# AnalogPSU.net
KiCad netlist of a schematic drawn in EAGLE
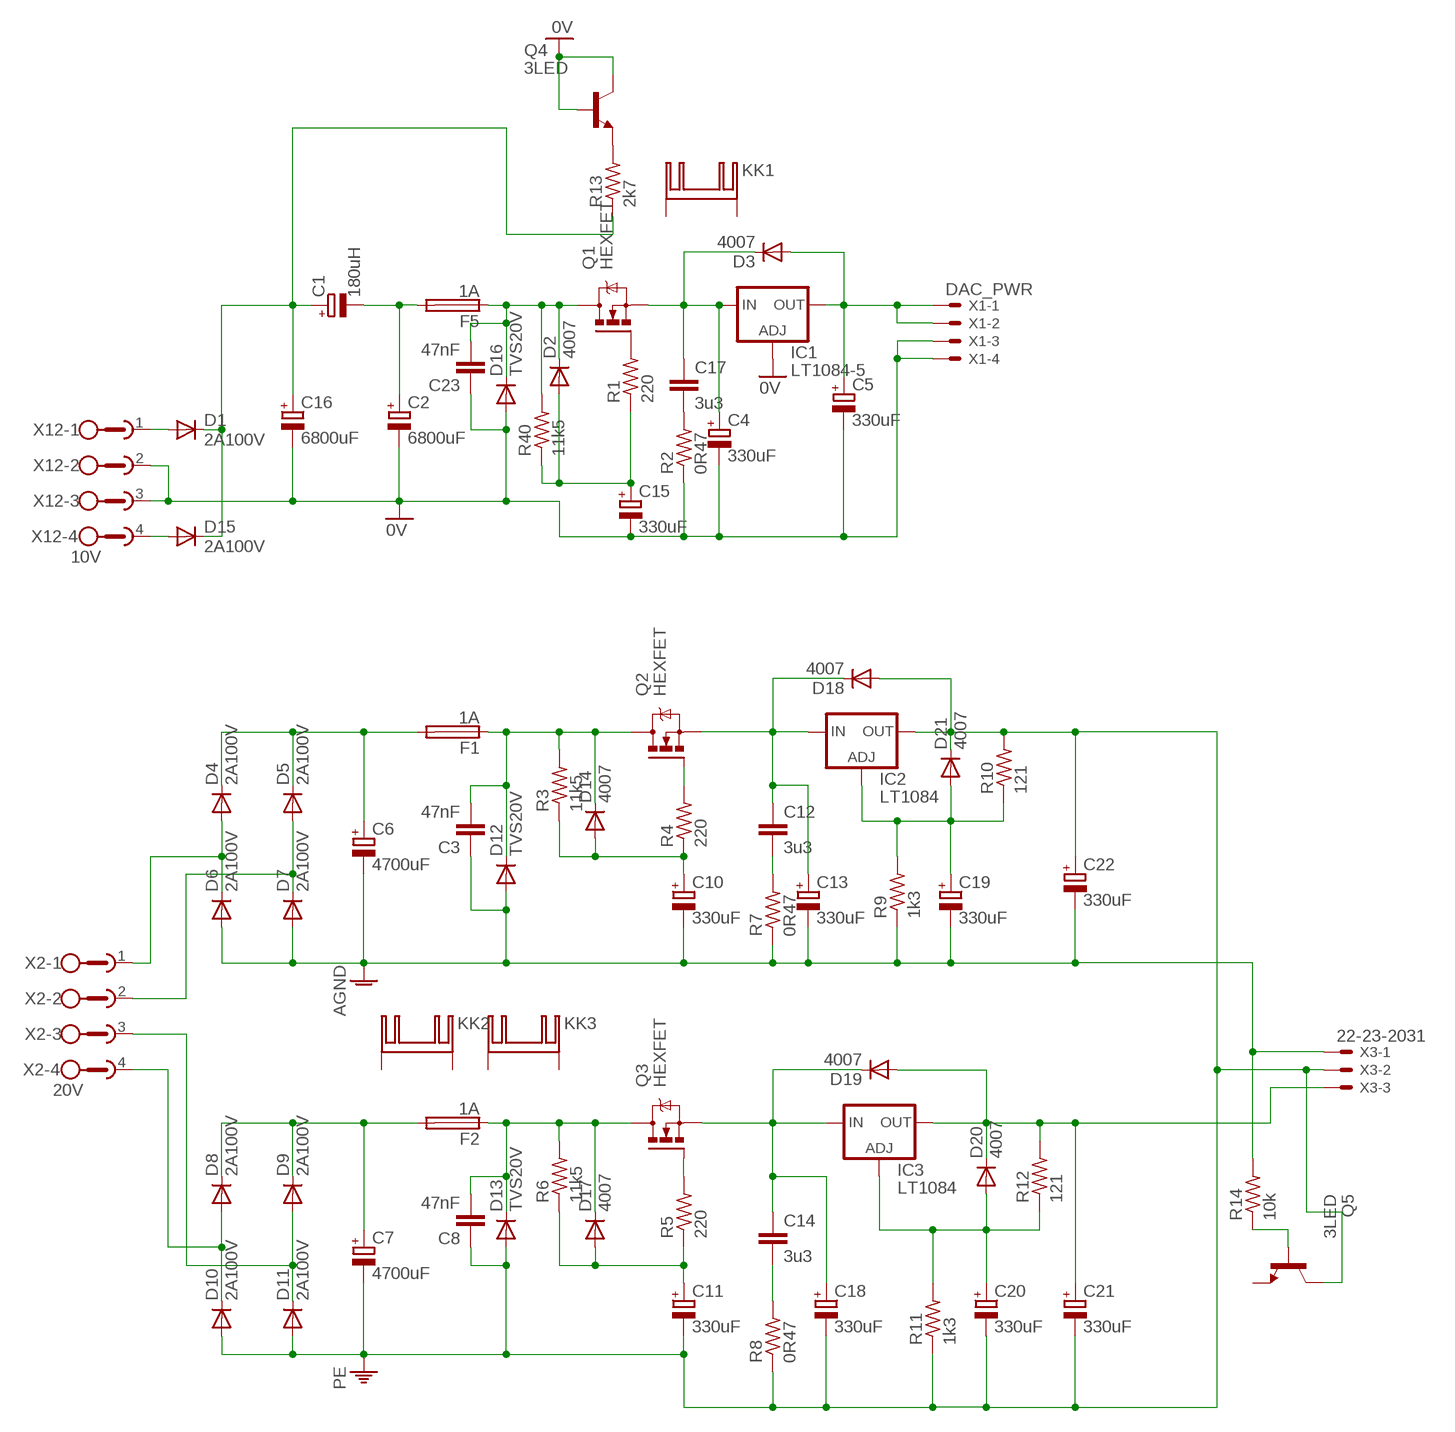
[diagram p0: schematic, sheet 1]

(export (version "E")
  (design (tool "Eeschema 10.0.6"))
  (components
    (comp (ref "C1")
      (value "180uH")
      (footprint "eagle-import:B45181C")
      (libsource (lib "eagle-import") (part "CPOL-EUB45181C"))
    )
    (comp (ref "C2")
      (value "6800uF")
      (footprint "eagle-import:EB20D")
      (libsource (lib "eagle-import") (part "CPOL-EUE10-20"))
    )
    (comp (ref "C3")
      (value "47nF")
      (footprint "eagle-import:C050-075X075")
      (libsource (lib "eagle-import") (part "C-EU050-075X075"))
    )
    (comp (ref "C4")
      (value "330uF")
      (footprint "eagle-import:E3,5-10")
      (libsource (lib "eagle-import") (part "CPOL-EUE3.5-10"))
    )
    (comp (ref "C5")
      (value "330uF")
      (footprint "eagle-import:E3,5-10")
      (libsource (lib "eagle-import") (part "CPOL-EUE3.5-10"))
    )
    (comp (ref "C6")
      (value "4700uF")
      (footprint "eagle-import:EB20D")
      (libsource (lib "eagle-import") (part "CPOL-EUE10-20"))
    )
    (comp (ref "C7")
      (value "4700uF")
      (footprint "eagle-import:EB20D")
      (libsource (lib "eagle-import") (part "CPOL-EUE10-20"))
    )
    (comp (ref "C8")
      (value "47nF")
      (footprint "eagle-import:C050-075X075")
      (libsource (lib "eagle-import") (part "C-EU050-075X075"))
    )
    (comp (ref "C10")
      (value "330uF")
      (footprint "eagle-import:E3,5-10")
      (libsource (lib "eagle-import") (part "CPOL-EUE3.5-10"))
    )
    (comp (ref "C11")
      (value "330uF")
      (footprint "eagle-import:E3,5-10")
      (libsource (lib "eagle-import") (part "CPOL-EUE3.5-10"))
    )
    (comp (ref "C12")
      (value "3u3")
      (footprint "eagle-import:C27.5B13")
      (libsource (lib "eagle-import") (part "C27/13"))
    )
    (comp (ref "C13")
      (value "330uF")
      (footprint "eagle-import:E3,5-10")
      (libsource (lib "eagle-import") (part "CPOL-EUE3.5-10"))
    )
    (comp (ref "C14")
      (value "3u3")
      (footprint "eagle-import:C27.5B13")
      (libsource (lib "eagle-import") (part "C27/13"))
    )
    (comp (ref "C15")
      (value "330uF")
      (footprint "eagle-import:E3,5-10")
      (libsource (lib "eagle-import") (part "CPOL-EUE3.5-10"))
    )
    (comp (ref "C16")
      (value "6800uF")
      (footprint "eagle-import:EB20D")
      (libsource (lib "eagle-import") (part "CPOL-EUE10-20"))
    )
    (comp (ref "C17")
      (value "3u3")
      (footprint "eagle-import:C27.5B13")
      (libsource (lib "eagle-import") (part "C27/13"))
    )
    (comp (ref "C18")
      (value "330uF")
      (footprint "eagle-import:E3,5-10")
      (libsource (lib "eagle-import") (part "CPOL-EUE3.5-10"))
    )
    (comp (ref "C19")
      (value "330uF")
      (footprint "eagle-import:E3,5-10")
      (libsource (lib "eagle-import") (part "CPOL-EUE3.5-10"))
    )
    (comp (ref "C20")
      (value "330uF")
      (footprint "eagle-import:E3,5-10")
      (libsource (lib "eagle-import") (part "CPOL-EUE3.5-10"))
    )
    (comp (ref "C21")
      (value "330uF")
      (footprint "eagle-import:E3,5-10")
      (libsource (lib "eagle-import") (part "CPOL-EUE3.5-10"))
    )
    (comp (ref "C22")
      (value "330uF")
      (footprint "eagle-import:E3,5-10")
      (libsource (lib "eagle-import") (part "CPOL-EUE3.5-10"))
    )
    (comp (ref "C23")
      (value "47nF")
      (footprint "eagle-import:C050-075X075")
      (libsource (lib "eagle-import") (part "C-EU050-075X075"))
    )
    (comp (ref "D1")
      (value "2A100V")
      (footprint "eagle-import:DO41-10")
      (libsource (lib "eagle-import") (part "1N4004"))
    )
    (comp (ref "D2")
      (value "4007")
      (footprint "eagle-import:DO35-10")
      (libsource (lib "eagle-import") (part "1N4148DO35-10"))
    )
    (comp (ref "D3")
      (value "4007")
      (footprint "eagle-import:DO35-10")
      (libsource (lib "eagle-import") (part "1N4148DO35-10"))
    )
    (comp (ref "D4")
      (value "2A100V")
      (footprint "eagle-import:DO41-10")
      (libsource (lib "eagle-import") (part "1N4004"))
    )
    (comp (ref "D5")
      (value "2A100V")
      (footprint "eagle-import:DO41-10")
      (libsource (lib "eagle-import") (part "1N4004"))
    )
    (comp (ref "D6")
      (value "2A100V")
      (footprint "eagle-import:DO41-10")
      (libsource (lib "eagle-import") (part "1N4004"))
    )
    (comp (ref "D7")
      (value "2A100V")
      (footprint "eagle-import:DO41-10")
      (libsource (lib "eagle-import") (part "1N4004"))
    )
    (comp (ref "D8")
      (value "2A100V")
      (footprint "eagle-import:DO41-10")
      (libsource (lib "eagle-import") (part "1N4004"))
    )
    (comp (ref "D9")
      (value "2A100V")
      (footprint "eagle-import:DO41-10")
      (libsource (lib "eagle-import") (part "1N4004"))
    )
    (comp (ref "D10")
      (value "2A100V")
      (footprint "eagle-import:DO41-10")
      (libsource (lib "eagle-import") (part "1N4004"))
    )
    (comp (ref "D11")
      (value "2A100V")
      (footprint "eagle-import:DO41-10")
      (libsource (lib "eagle-import") (part "1N4004"))
    )
    (comp (ref "D12")
      (value "TVS20V")
      (footprint "eagle-import:SOD57-10")
      (libsource (lib "eagle-import") (part "BY448"))
    )
    (comp (ref "D13")
      (value "TVS20V")
      (footprint "eagle-import:SOD57-10")
      (libsource (lib "eagle-import") (part "BY448"))
    )
    (comp (ref "D14")
      (value "4007")
      (footprint "eagle-import:DO35-10")
      (libsource (lib "eagle-import") (part "1N4148DO35-10"))
    )
    (comp (ref "D15")
      (value "2A100V")
      (footprint "eagle-import:DO41-10")
      (libsource (lib "eagle-import") (part "1N4004"))
    )
    (comp (ref "D16")
      (value "TVS20V")
      (footprint "eagle-import:SOD57-10")
      (libsource (lib "eagle-import") (part "BY448"))
    )
    (comp (ref "D17")
      (value "4007")
      (footprint "eagle-import:DO35-10")
      (libsource (lib "eagle-import") (part "1N4148DO35-10"))
    )
    (comp (ref "D18")
      (value "4007")
      (footprint "eagle-import:DO35-7")
      (libsource (lib "eagle-import") (part "1N4148DO35-7"))
    )
    (comp (ref "D19")
      (value "4007")
      (footprint "eagle-import:DO35-7")
      (libsource (lib "eagle-import") (part "1N4148DO35-7"))
    )
    (comp (ref "D20")
      (value "4007")
      (footprint "eagle-import:DO35-7")
      (libsource (lib "eagle-import") (part "1N4148DO35-7"))
    )
    (comp (ref "D21")
      (value "4007")
      (footprint "eagle-import:DO35-7")
      (libsource (lib "eagle-import") (part "1N4148DO35-7"))
    )
    (comp (ref "F1")
      (value "1A")
      (footprint "eagle-import:19560")
      (fields (field (name "MPN") "56000001009"))
      (libsource (lib "eagle-import") (part "19560"))
    )
    (comp (ref "F2")
      (value "1A")
      (footprint "eagle-import:19560")
      (fields (field (name "MPN") "56000001009"))
      (libsource (lib "eagle-import") (part "19560"))
    )
    (comp (ref "F5")
      (value "1A")
      (footprint "eagle-import:19560")
      (fields (field (name "MPN") "56000001009"))
      (libsource (lib "eagle-import") (part "19560"))
    )
    (comp (ref "IC1")
      (value "LT1084-5")
      (footprint "eagle-import:317TS")
      (libsource (lib "eagle-import") (part "LM317TS"))
    )
    (comp (ref "IC2")
      (value "LT1084")
      (footprint "eagle-import:317TS")
      (libsource (lib "eagle-import") (part "LM317TS"))
    )
    (comp (ref "IC3")
      (value "LT1084")
      (footprint "eagle-import:317TS")
      (libsource (lib "eagle-import") (part "LM317TS"))
    )
    (comp (ref "KK1")
      (value "SK104-PAD")
      (footprint "eagle-import:SK104-PAD")
      (libsource (lib "eagle-import") (part "SK104-PAD"))
    )
    (comp (ref "KK2")
      (value "SK104-PAD")
      (footprint "eagle-import:SK104-PAD")
      (libsource (lib "eagle-import") (part "SK104-PAD"))
    )
    (comp (ref "KK3")
      (value "SK104-PAD")
      (footprint "eagle-import:SK104-PAD")
      (libsource (lib "eagle-import") (part "SK104-PAD"))
    )
    (comp (ref "Q1")
      (value "HEXFET")
      (footprint "eagle-import:TO220BV")
      (libsource (lib "eagle-import") (part "IRF520"))
    )
    (comp (ref "Q2")
      (value "HEXFET")
      (footprint "eagle-import:TO220BV")
      (libsource (lib "eagle-import") (part "IRF520"))
    )
    (comp (ref "Q3")
      (value "HEXFET")
      (footprint "eagle-import:TO220BV")
      (libsource (lib "eagle-import") (part "IRF520"))
    )
    (comp (ref "Q4")
      (value "3LED")
      (footprint "eagle-import:TO92-EBC")
      (libsource (lib "eagle-import") (part "BC546A"))
    )
    (comp (ref "Q5")
      (value "3LED")
      (footprint "eagle-import:TO92-EBC")
      (libsource (lib "eagle-import") (part "BC546A"))
    )
    (comp (ref "R1")
      (value "220")
      (footprint "eagle-import:0309_10")
      (libsource (lib "eagle-import") (part "R-US_0309/10"))
    )
    (comp (ref "R2")
      (value "0R47")
      (footprint "eagle-import:0617V")
      (libsource (lib "eagle-import") (part "R-US_0617/5V"))
    )
    (comp (ref "R3")
      (value "11k5")
      (footprint "eagle-import:0309_10")
      (libsource (lib "eagle-import") (part "R-US_0309/10"))
    )
    (comp (ref "R4")
      (value "220")
      (footprint "eagle-import:0309_10")
      (libsource (lib "eagle-import") (part "R-US_0309/10"))
    )
    (comp (ref "R5")
      (value "220")
      (footprint "eagle-import:0309_10")
      (libsource (lib "eagle-import") (part "R-US_0309/10"))
    )
    (comp (ref "R6")
      (value "11k5")
      (footprint "eagle-import:0309_10")
      (libsource (lib "eagle-import") (part "R-US_0309/10"))
    )
    (comp (ref "R7")
      (value "0R47")
      (footprint "eagle-import:0617V")
      (libsource (lib "eagle-import") (part "R-US_0617/5V"))
    )
    (comp (ref "R8")
      (value "0R47")
      (footprint "eagle-import:0617V")
      (libsource (lib "eagle-import") (part "R-US_0617/5V"))
    )
    (comp (ref "R9")
      (value "1k3")
      (footprint "eagle-import:0309_10")
      (libsource (lib "eagle-import") (part "R-US_0309/10"))
    )
    (comp (ref "R10")
      (value "121")
      (footprint "eagle-import:0309_10")
      (libsource (lib "eagle-import") (part "R-US_0309/10"))
    )
    (comp (ref "R11")
      (value "1k3")
      (footprint "eagle-import:0309_10")
      (libsource (lib "eagle-import") (part "R-US_0309/10"))
    )
    (comp (ref "R12")
      (value "121")
      (footprint "eagle-import:0309_10")
      (libsource (lib "eagle-import") (part "R-US_0309/10"))
    )
    (comp (ref "R13")
      (value "2k7")
      (footprint "eagle-import:0309_12")
      (libsource (lib "eagle-import") (part "R-US_0309/12"))
    )
    (comp (ref "R14")
      (value "10k")
      (footprint "eagle-import:0309_10")
      (libsource (lib "eagle-import") (part "R-US_0309/10"))
    )
    (comp (ref "R40")
      (value "11k5")
      (footprint "eagle-import:0309_10")
      (libsource (lib "eagle-import") (part "R-US_0309/10"))
    )
    (comp (ref "X1")
      (value "DAC_PWR")
      (footprint "eagle-import:22-23-2041")
      (fields (field (name "MF") "MOLEX") (field (name "MPN") "22-23-2041"))
      (libsource (lib "eagle-import") (part "22-23-2041"))
    )
    (comp (ref "X2")
      (value "20V")
      (footprint "eagle-import:GMSTBA4")
      (fields (field (name "MF") "FARNELL") (field (name "MPN") "1757268"))
      (libsource (lib "eagle-import") (part "GMSTBA4"))
    )
    (comp (ref "X3")
      (value "22-23-2031")
      (footprint "eagle-import:22-23-2031")
      (fields (field (name "MF") "MOLEX"))
      (libsource (lib "eagle-import") (part "22-23-2031"))
    )
    (comp (ref "X12")
      (value "10V")
      (footprint "eagle-import:GMSTBA4")
      (fields (field (name "MF") "FARNELL") (field (name "MPN") "1757268"))
      (libsource (lib "eagle-import") (part "GMSTBA4"))
    )
  )
  (nets
    (net (code "1") (name "0V") (class "Default")
      (node (ref "C15") (pin "-") (pinfunction "-_-") (pintype "passive"))
      (node (ref "C16") (pin "-") (pinfunction "-_-") (pintype "passive"))
      (node (ref "C2") (pin "-") (pinfunction "-_-") (pintype "passive"))
      (node (ref "C23") (pin "1") (pinfunction "1_1") (pintype "passive"))
      (node (ref "C4") (pin "-") (pinfunction "-_-") (pintype "passive"))
      (node (ref "C5") (pin "-") (pinfunction "-_-") (pintype "passive"))
      (node (ref "D16") (pin "A") (pinfunction "A_A") (pintype "passive"))
      (node (ref "IC1") (pin "1") (pinfunction "ADJ_1") (pintype "input"))
      (node (ref "Q4") (pin "B") (pinfunction "B_B") (pintype "passive"))
      (node (ref "Q4") (pin "C") (pinfunction "C_C") (pintype "passive"))
      (node (ref "R2") (pin "1") (pinfunction "1_1") (pintype "passive"))
      (node (ref "X1") (pin "3") (pinfunction "S_3") (pintype "passive"))
      (node (ref "X1") (pin "4") (pinfunction "S_4") (pintype "passive"))
      (node (ref "X12") (pin "2") (pinfunction "1_2") (pintype "passive"))
      (node (ref "X12") (pin "3") (pinfunction "1_3") (pintype "passive"))
    )
    (net (code "2") (name "AGND") (class "Default")
      (node (ref "C10") (pin "-") (pinfunction "-_-") (pintype "passive"))
      (node (ref "C13") (pin "-") (pinfunction "-_-") (pintype "passive"))
      (node (ref "C19") (pin "-") (pinfunction "-_-") (pintype "passive"))
      (node (ref "C22") (pin "-") (pinfunction "-_-") (pintype "passive"))
      (node (ref "C3") (pin "1") (pinfunction "1_1") (pintype "passive"))
      (node (ref "C6") (pin "-") (pinfunction "-_-") (pintype "passive"))
      (node (ref "D12") (pin "A") (pinfunction "A_A") (pintype "passive"))
      (node (ref "D6") (pin "A") (pinfunction "A_A") (pintype "passive"))
      (node (ref "D7") (pin "A") (pinfunction "A_A") (pintype "passive"))
      (node (ref "R14") (pin "2") (pinfunction "2_2") (pintype "passive"))
      (node (ref "R7") (pin "1") (pinfunction "1_1") (pintype "passive"))
      (node (ref "R9") (pin "1") (pinfunction "1_1") (pintype "passive"))
      (node (ref "X3") (pin "1") (pinfunction "S_1") (pintype "passive"))
    )
    (net (code "3") (name "Net-(C1-Pad+)") (class "Default")
      (node (ref "C1") (pin "+") (pinfunction "+_+") (pintype "passive"))
      (node (ref "C16") (pin "+") (pinfunction "+_+") (pintype "passive"))
      (node (ref "D1") (pin "C") (pinfunction "C_C") (pintype "passive"))
      (node (ref "D15") (pin "C") (pinfunction "C_C") (pintype "passive"))
      (node (ref "R13") (pin "1") (pinfunction "1_1") (pintype "passive"))
    )
    (net (code "4") (name "Net-(C1-Pad-)") (class "Default")
      (node (ref "C1") (pin "-") (pinfunction "-_-") (pintype "passive"))
      (node (ref "C2") (pin "+") (pinfunction "+_+") (pintype "passive"))
      (node (ref "F5") (pin "2") (pinfunction "2_2") (pintype "passive"))
    )
    (net (code "5") (name "Net-(C3-Pad2)") (class "Default")
      (node (ref "C3") (pin "2") (pinfunction "2_2") (pintype "passive"))
      (node (ref "D12") (pin "C") (pinfunction "C_C") (pintype "passive"))
      (node (ref "D14") (pin "C") (pinfunction "C_C") (pintype "passive"))
      (node (ref "F1") (pin "1") (pinfunction "1_1") (pintype "passive"))
      (node (ref "Q2") (pin "D") (pinfunction "D_D") (pintype "passive"))
      (node (ref "R3") (pin "2") (pinfunction "2_2") (pintype "passive"))
    )
    (net (code "6") (name "Net-(C6-Pad+)") (class "Default")
      (node (ref "C6") (pin "+") (pinfunction "+_+") (pintype "passive"))
      (node (ref "D4") (pin "C") (pinfunction "C_C") (pintype "passive"))
      (node (ref "D5") (pin "C") (pinfunction "C_C") (pintype "passive"))
      (node (ref "F1") (pin "2") (pinfunction "2_2") (pintype "passive"))
    )
    (net (code "7") (name "Net-(C7-Pad+)") (class "Default")
      (node (ref "C7") (pin "+") (pinfunction "+_+") (pintype "passive"))
      (node (ref "D8") (pin "C") (pinfunction "C_C") (pintype "passive"))
      (node (ref "D9") (pin "C") (pinfunction "C_C") (pintype "passive"))
      (node (ref "F2") (pin "2") (pinfunction "2_2") (pintype "passive"))
    )
    (net (code "8") (name "Net-(C8-Pad2)") (class "Default")
      (node (ref "C8") (pin "2") (pinfunction "2_2") (pintype "passive"))
      (node (ref "D13") (pin "C") (pinfunction "C_C") (pintype "passive"))
      (node (ref "D17") (pin "C") (pinfunction "C_C") (pintype "passive"))
      (node (ref "F2") (pin "1") (pinfunction "1_1") (pintype "passive"))
      (node (ref "Q3") (pin "D") (pinfunction "D_D") (pintype "passive"))
      (node (ref "R6") (pin "2") (pinfunction "2_2") (pintype "passive"))
    )
    (net (code "9") (name "Net-(C10-Pad+)") (class "Default")
      (node (ref "C10") (pin "+") (pinfunction "+_+") (pintype "passive"))
      (node (ref "D14") (pin "A") (pinfunction "A_A") (pintype "passive"))
      (node (ref "R3") (pin "1") (pinfunction "1_1") (pintype "passive"))
      (node (ref "R4") (pin "1") (pinfunction "1_1") (pintype "passive"))
    )
    (net (code "10") (name "Net-(C11-Pad+)") (class "Default")
      (node (ref "C11") (pin "+") (pinfunction "+_+") (pintype "passive"))
      (node (ref "D17") (pin "A") (pinfunction "A_A") (pintype "passive"))
      (node (ref "R5") (pin "1") (pinfunction "1_1") (pintype "passive"))
      (node (ref "R6") (pin "1") (pinfunction "1_1") (pintype "passive"))
    )
    (net (code "11") (name "Net-(C12-Pad2)") (class "Default")
      (node (ref "C12") (pin "2") (pinfunction "2_2") (pintype "passive"))
      (node (ref "R7") (pin "2") (pinfunction "2_2") (pintype "passive"))
    )
    (net (code "12") (name "Net-(C14-Pad2)") (class "Default")
      (node (ref "C14") (pin "2") (pinfunction "2_2") (pintype "passive"))
      (node (ref "R8") (pin "2") (pinfunction "2_2") (pintype "passive"))
    )
    (net (code "13") (name "Net-(C15-Pad+)") (class "Default")
      (node (ref "C15") (pin "+") (pinfunction "+_+") (pintype "passive"))
      (node (ref "D2") (pin "A") (pinfunction "A_A") (pintype "passive"))
      (node (ref "R1") (pin "1") (pinfunction "1_1") (pintype "passive"))
      (node (ref "R40") (pin "1") (pinfunction "1_1") (pintype "passive"))
    )
    (net (code "14") (name "Net-(C17-Pad2)") (class "Default")
      (node (ref "C17") (pin "2") (pinfunction "2_2") (pintype "passive"))
      (node (ref "R2") (pin "2") (pinfunction "2_2") (pintype "passive"))
    )
    (net (code "15") (name "Net-(C23-Pad2)") (class "Default")
      (node (ref "C23") (pin "2") (pinfunction "2_2") (pintype "passive"))
      (node (ref "D16") (pin "C") (pinfunction "C_C") (pintype "passive"))
      (node (ref "D2") (pin "C") (pinfunction "C_C") (pintype "passive"))
      (node (ref "F5") (pin "1") (pinfunction "1_1") (pintype "passive"))
      (node (ref "Q1") (pin "D") (pinfunction "D_D") (pintype "passive"))
      (node (ref "R40") (pin "2") (pinfunction "2_2") (pintype "passive"))
    )
    (net (code "16") (name "Net-(D1-PadA)") (class "Default")
      (node (ref "D1") (pin "A") (pinfunction "A_A") (pintype "passive"))
      (node (ref "X12") (pin "1") (pinfunction "1_1") (pintype "passive"))
    )
    (net (code "17") (name "Net-(D4-PadA)") (class "Default")
      (node (ref "D4") (pin "A") (pinfunction "A_A") (pintype "passive"))
      (node (ref "D6") (pin "C") (pinfunction "C_C") (pintype "passive"))
      (node (ref "X2") (pin "1") (pinfunction "1_1") (pintype "passive"))
    )
    (net (code "18") (name "Net-(IC1-IN)") (class "Default")
      (node (ref "C17") (pin "1") (pinfunction "1_1") (pintype "passive"))
      (node (ref "C4") (pin "+") (pinfunction "+_+") (pintype "passive"))
      (node (ref "D3") (pin "C") (pinfunction "C_C") (pintype "passive"))
      (node (ref "IC1") (pin "3") (pinfunction "IN_3") (pintype "input"))
      (node (ref "Q1") (pin "S") (pinfunction "S_S") (pintype "passive"))
    )
    (net (code "19") (name "Net-(IC1-OUT)") (class "Default")
      (node (ref "C5") (pin "+") (pinfunction "+_+") (pintype "passive"))
      (node (ref "D3") (pin "A") (pinfunction "A_A") (pintype "passive"))
      (node (ref "IC1") (pin "2") (pinfunction "OUT_2") (pintype "passive"))
      (node (ref "X1") (pin "1") (pinfunction "S_1") (pintype "passive"))
      (node (ref "X1") (pin "2") (pinfunction "S_2") (pintype "passive"))
    )
    (net (code "20") (name "Net-(IC2-ADJ)") (class "Default")
      (node (ref "C19") (pin "+") (pinfunction "+_+") (pintype "passive"))
      (node (ref "D21") (pin "A") (pinfunction "A_A") (pintype "passive"))
      (node (ref "IC2") (pin "1") (pinfunction "ADJ_1") (pintype "input"))
      (node (ref "R10") (pin "1") (pinfunction "1_1") (pintype "passive"))
      (node (ref "R9") (pin "2") (pinfunction "2_2") (pintype "passive"))
    )
    (net (code "21") (name "Net-(IC2-IN)") (class "Default")
      (node (ref "C12") (pin "1") (pinfunction "1_1") (pintype "passive"))
      (node (ref "C13") (pin "+") (pinfunction "+_+") (pintype "passive"))
      (node (ref "D18") (pin "C") (pinfunction "C_C") (pintype "passive"))
      (node (ref "IC2") (pin "3") (pinfunction "IN_3") (pintype "input"))
      (node (ref "Q2") (pin "S") (pinfunction "S_S") (pintype "passive"))
    )
    (net (code "22") (name "Net-(IC3-ADJ)") (class "Default")
      (node (ref "C20") (pin "+") (pinfunction "+_+") (pintype "passive"))
      (node (ref "D20") (pin "A") (pinfunction "A_A") (pintype "passive"))
      (node (ref "IC3") (pin "1") (pinfunction "ADJ_1") (pintype "input"))
      (node (ref "R11") (pin "2") (pinfunction "2_2") (pintype "passive"))
      (node (ref "R12") (pin "1") (pinfunction "1_1") (pintype "passive"))
    )
    (net (code "23") (name "Net-(IC3-IN)") (class "Default")
      (node (ref "C14") (pin "1") (pinfunction "1_1") (pintype "passive"))
      (node (ref "C18") (pin "+") (pinfunction "+_+") (pintype "passive"))
      (node (ref "D19") (pin "C") (pinfunction "C_C") (pintype "passive"))
      (node (ref "IC3") (pin "3") (pinfunction "IN_3") (pintype "input"))
      (node (ref "Q3") (pin "S") (pinfunction "S_S") (pintype "passive"))
    )
    (net (code "24") (name "Net-(IC3-OUT)") (class "Default")
      (node (ref "C21") (pin "+") (pinfunction "+_+") (pintype "passive"))
      (node (ref "D19") (pin "A") (pinfunction "A_A") (pintype "passive"))
      (node (ref "D20") (pin "C") (pinfunction "C_C") (pintype "passive"))
      (node (ref "IC3") (pin "2") (pinfunction "OUT_2") (pintype "passive"))
      (node (ref "R12") (pin "2") (pinfunction "2_2") (pintype "passive"))
      (node (ref "X3") (pin "3") (pinfunction "S_3") (pintype "passive"))
    )
    (net (code "25") (name "Net-(Q1-PadG)") (class "Default")
      (node (ref "Q1") (pin "G") (pinfunction "G_G") (pintype "passive"))
      (node (ref "R1") (pin "2") (pinfunction "2_2") (pintype "passive"))
    )
    (net (code "26") (name "Net-(Q2-PadG)") (class "Default")
      (node (ref "Q2") (pin "G") (pinfunction "G_G") (pintype "passive"))
      (node (ref "R4") (pin "2") (pinfunction "2_2") (pintype "passive"))
    )
    (net (code "27") (name "Net-(Q3-PadG)") (class "Default")
      (node (ref "Q3") (pin "G") (pinfunction "G_G") (pintype "passive"))
      (node (ref "R5") (pin "2") (pinfunction "2_2") (pintype "passive"))
    )
    (net (code "28") (name "Net-(Q4-PadE)") (class "Default")
      (node (ref "Q4") (pin "E") (pinfunction "E_E") (pintype "passive"))
      (node (ref "R13") (pin "2") (pinfunction "2_2") (pintype "passive"))
    )
    (net (code "29") (name "Net-(Q5-PadB)") (class "Default")
      (node (ref "Q5") (pin "B") (pinfunction "B_B") (pintype "passive"))
      (node (ref "R14") (pin "1") (pinfunction "1_1") (pintype "passive"))
    )
    (net (code "30") (name "Net-(X2B-1)") (class "Default")
      (node (ref "D5") (pin "A") (pinfunction "A_A") (pintype "passive"))
      (node (ref "D7") (pin "C") (pinfunction "C_C") (pintype "passive"))
      (node (ref "X2") (pin "2") (pinfunction "1_2") (pintype "passive"))
    )
    (net (code "31") (name "Net-(X2C-1)") (class "Default")
      (node (ref "D11") (pin "C") (pinfunction "C_C") (pintype "passive"))
      (node (ref "D9") (pin "A") (pinfunction "A_A") (pintype "passive"))
      (node (ref "X2") (pin "3") (pinfunction "1_3") (pintype "passive"))
    )
    (net (code "32") (name "Net-(X2D-1)") (class "Default")
      (node (ref "D10") (pin "C") (pinfunction "C_C") (pintype "passive"))
      (node (ref "D8") (pin "A") (pinfunction "A_A") (pintype "passive"))
      (node (ref "X2") (pin "4") (pinfunction "1_4") (pintype "passive"))
    )
    (net (code "33") (name "Net-(X12D-1)") (class "Default")
      (node (ref "D15") (pin "A") (pinfunction "A_A") (pintype "passive"))
      (node (ref "X12") (pin "4") (pinfunction "1_4") (pintype "passive"))
    )
    (net (code "34") (name "PE") (class "Default")
      (node (ref "C11") (pin "-") (pinfunction "-_-") (pintype "passive"))
      (node (ref "C18") (pin "-") (pinfunction "-_-") (pintype "passive"))
      (node (ref "C20") (pin "-") (pinfunction "-_-") (pintype "passive"))
      (node (ref "C21") (pin "-") (pinfunction "-_-") (pintype "passive"))
      (node (ref "C22") (pin "+") (pinfunction "+_+") (pintype "passive"))
      (node (ref "C7") (pin "-") (pinfunction "-_-") (pintype "passive"))
      (node (ref "C8") (pin "1") (pinfunction "1_1") (pintype "passive"))
      (node (ref "D10") (pin "A") (pinfunction "A_A") (pintype "passive"))
      (node (ref "D11") (pin "A") (pinfunction "A_A") (pintype "passive"))
      (node (ref "D13") (pin "A") (pinfunction "A_A") (pintype "passive"))
      (node (ref "D18") (pin "A") (pinfunction "A_A") (pintype "passive"))
      (node (ref "D21") (pin "C") (pinfunction "C_C") (pintype "passive"))
      (node (ref "IC2") (pin "2") (pinfunction "OUT_2") (pintype "passive"))
      (node (ref "Q5") (pin "C") (pinfunction "C_C") (pintype "passive"))
      (node (ref "R10") (pin "2") (pinfunction "2_2") (pintype "passive"))
      (node (ref "R11") (pin "1") (pinfunction "1_1") (pintype "passive"))
      (node (ref "R8") (pin "1") (pinfunction "1_1") (pintype "passive"))
      (node (ref "X3") (pin "2") (pinfunction "S_2") (pintype "passive"))
    )
    (net (code "35") (name "unconnected-(KK1-K-PadK1)") (class "Default")
      (node (ref "KK1") (pin "K1") (pinfunction "K_K1") (pintype "passive"))
    )
    (net (code "36") (name "unconnected-(KK1-K-PadK2)") (class "Default")
      (node (ref "KK1") (pin "K2") (pinfunction "K_K2") (pintype "passive"))
    )
    (net (code "37") (name "unconnected-(KK2-K-PadK1)") (class "Default")
      (node (ref "KK2") (pin "K1") (pinfunction "K_K1") (pintype "passive"))
    )
    (net (code "38") (name "unconnected-(KK2-K-PadK2)") (class "Default")
      (node (ref "KK2") (pin "K2") (pinfunction "K_K2") (pintype "passive"))
    )
    (net (code "39") (name "unconnected-(KK3-K-PadK1)") (class "Default")
      (node (ref "KK3") (pin "K1") (pinfunction "K_K1") (pintype "passive"))
    )
    (net (code "40") (name "unconnected-(KK3-K-PadK2)") (class "Default")
      (node (ref "KK3") (pin "K2") (pinfunction "K_K2") (pintype "passive"))
    )
    (net (code "41") (name "unconnected-(Q5-PadE)") (class "Default")
      (node (ref "Q5") (pin "E") (pinfunction "E_E") (pintype "passive"))
    )
  )
)
